# ControlUnit_2.net
KiCad netlist of a schematic drawn in EAGLE
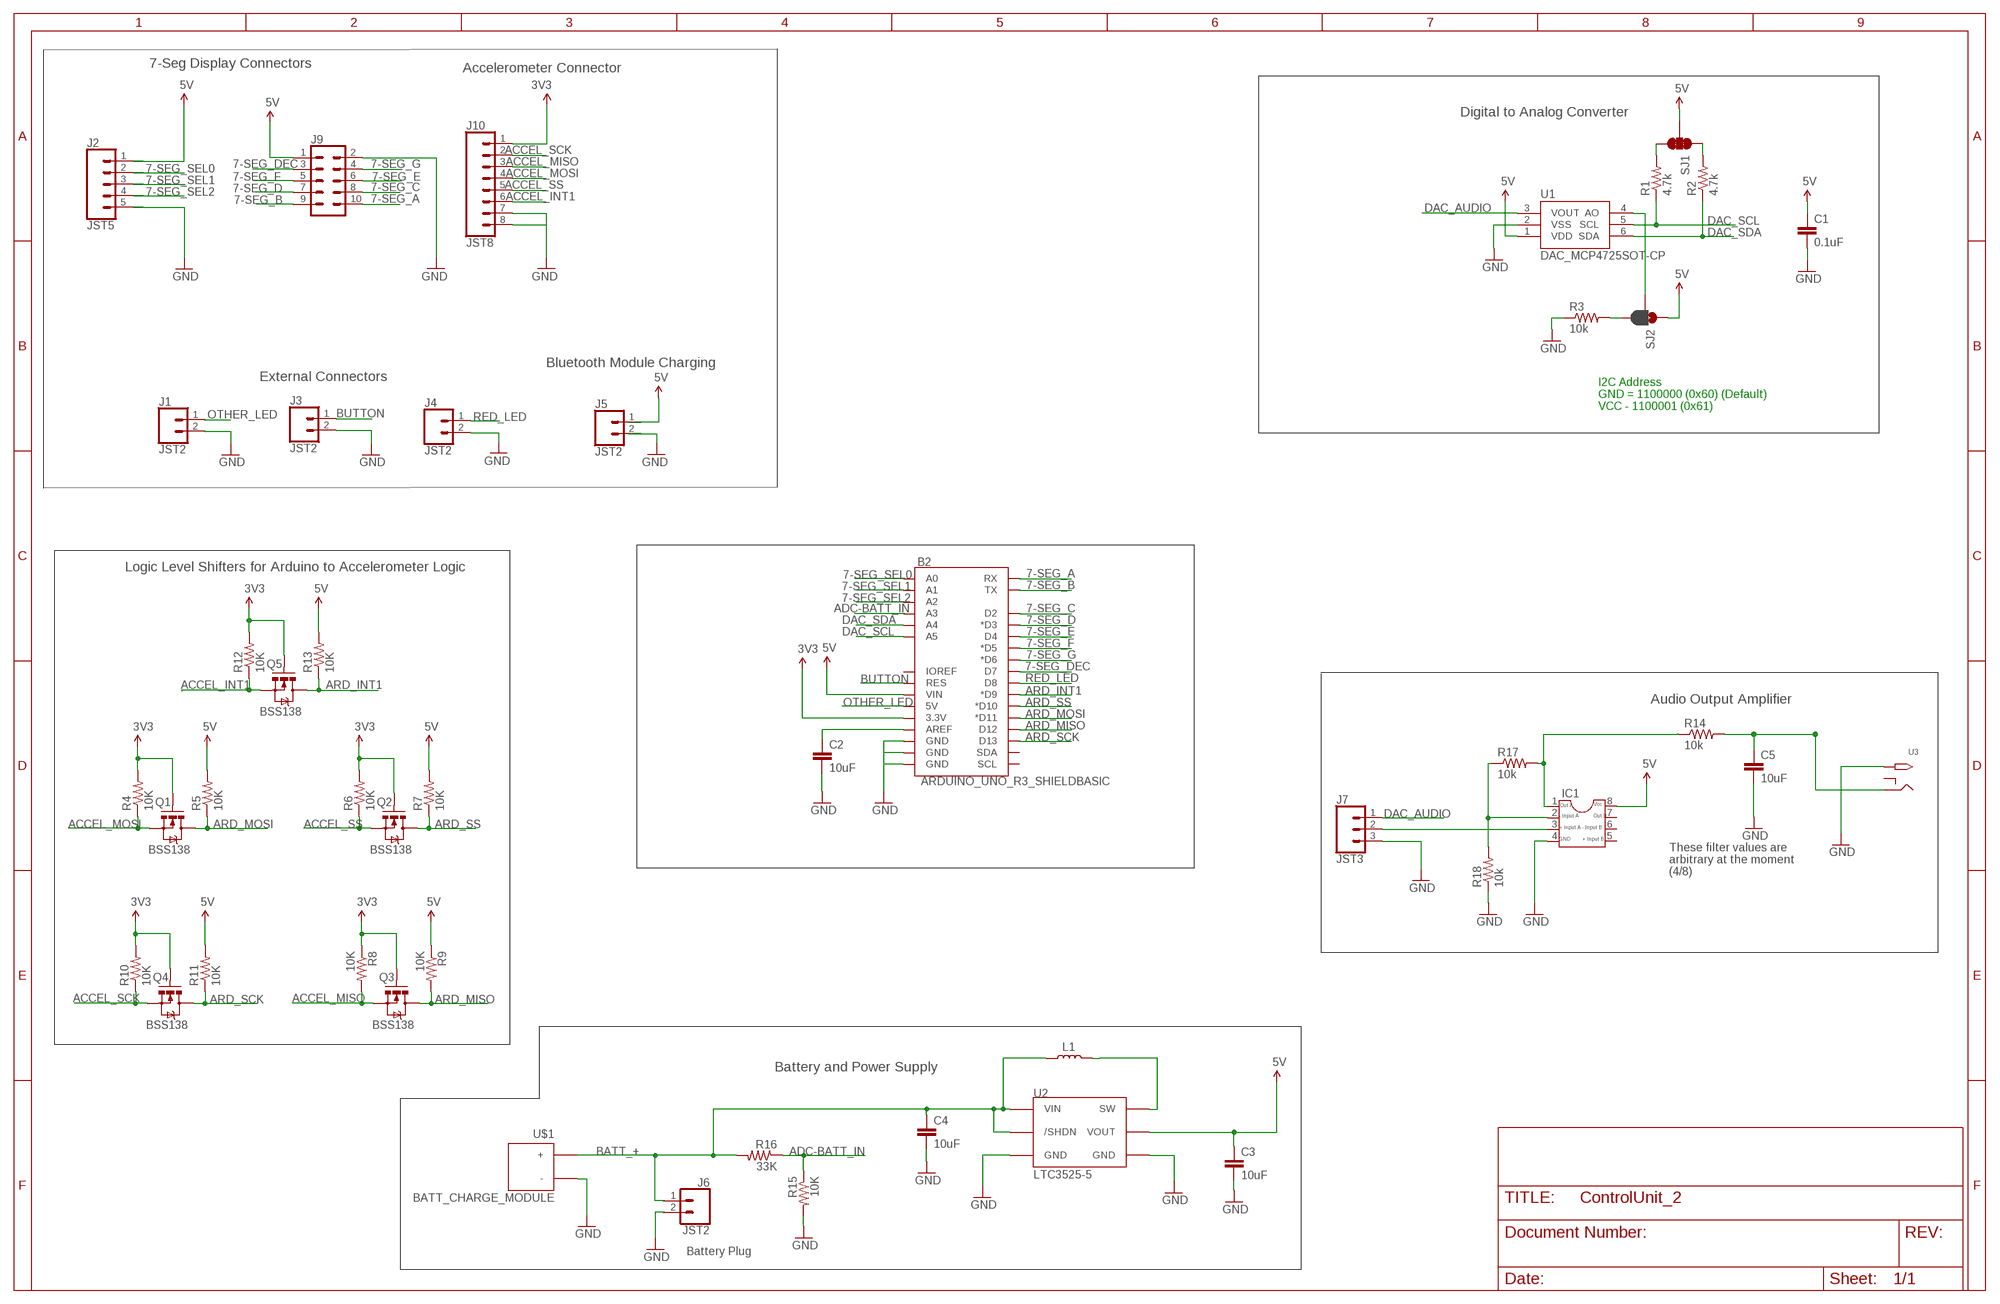
[diagram p0: schematic, sheet 1]

(export (version "E")
  (design (tool "Eeschema 10.0.6"))
  (components
    (comp (ref "B2")
      (value "ARDUINO_UNO_R3_SHIELDBASIC")
      (footprint "eagle-import:UNO_R3_SHIELD")
      (libsource (lib "eagle-import") (part "ARDUINO_UNO_R3_SHIELDBASIC"))
    )
    (comp (ref "C1")
      (value "0.1uF")
      (footprint "eagle-import:0603-CAP")
      (libsource (lib "eagle-import") (part "CAP0603-CAP"))
    )
    (comp (ref "C2")
      (value "10uF")
      (footprint "eagle-import:SPARKFUN_0805")
      (libsource (lib "eagle-import") (part "SPARKFUN_CAP0805"))
    )
    (comp (ref "C3")
      (value "10uF")
      (footprint "eagle-import:0603-CAP")
      (libsource (lib "eagle-import") (part "CAP0603-CAP"))
    )
    (comp (ref "C4")
      (value "10uF")
      (footprint "eagle-import:SPARKFUN_0805")
      (libsource (lib "eagle-import") (part "SPARKFUN_CAP0805"))
    )
    (comp (ref "C5")
      (value "10uF")
      (footprint "eagle-import:0603-CAP")
      (libsource (lib "eagle-import") (part "CAP0603-CAP"))
    )
    (comp (ref "IC1")
      (value "DIL8")
      (footprint "eagle-import:DIL08")
      (libsource (lib "eagle-import") (part "DIL8"))
    )
    (comp (ref "J1")
      (value "JST2")
      (footprint "eagle-import:2JST")
      (libsource (lib "eagle-import") (part "JST2"))
    )
    (comp (ref "J2")
      (value "JST5")
      (footprint "eagle-import:5JST")
      (libsource (lib "eagle-import") (part "JST5"))
    )
    (comp (ref "J3")
      (value "JST2")
      (footprint "eagle-import:2JST")
      (libsource (lib "eagle-import") (part "JST2"))
    )
    (comp (ref "J4")
      (value "JST2")
      (footprint "eagle-import:2JST")
      (libsource (lib "eagle-import") (part "JST2"))
    )
    (comp (ref "J5")
      (value "JST2")
      (footprint "eagle-import:2JST")
      (libsource (lib "eagle-import") (part "JST2"))
    )
    (comp (ref "J6")
      (value "JST2")
      (footprint "eagle-import:2JST")
      (libsource (lib "eagle-import") (part "JST2"))
    )
    (comp (ref "J7")
      (value "JST3")
      (footprint "eagle-import:3JST")
      (libsource (lib "eagle-import") (part "JST3"))
    )
    (comp (ref "J9")
      (value "CONN_05X2SHD_LOCK")
      (footprint "eagle-import:2X5-SHROUDED_LOCK")
      (libsource (lib "eagle-import") (part "CONN_05X2SHD_LOCK"))
    )
    (comp (ref "J10")
      (value "JST8")
      (footprint "eagle-import:8JST")
      (libsource (lib "eagle-import") (part "JST8"))
    )
    (comp (ref "L1")
      (value "10uH")
      (footprint "eagle-import:1210")
      (libsource (lib "eagle-import") (part "INDUCTOR"))
    )
    (comp (ref "Q1")
      (value "BSS138")
      (footprint "eagle-import:SOT23-3")
      (libsource (lib "eagle-import") (part "MOSFET-NCHANNELSMD"))
    )
    (comp (ref "Q2")
      (value "BSS138")
      (footprint "eagle-import:SOT23-3")
      (libsource (lib "eagle-import") (part "MOSFET-NCHANNELSMD"))
    )
    (comp (ref "Q3")
      (value "BSS138")
      (footprint "eagle-import:SOT23-3")
      (libsource (lib "eagle-import") (part "MOSFET-NCHANNELSMD"))
    )
    (comp (ref "Q4")
      (value "BSS138")
      (footprint "eagle-import:SOT23-3")
      (libsource (lib "eagle-import") (part "MOSFET-NCHANNELSMD"))
    )
    (comp (ref "Q5")
      (value "BSS138")
      (footprint "eagle-import:SOT23-3")
      (libsource (lib "eagle-import") (part "MOSFET-NCHANNELSMD"))
    )
    (comp (ref "R1")
      (value "4.7k")
      (footprint "eagle-import:0603-RES")
      (libsource (lib "eagle-import") (part "RESISTOR0603-RES"))
    )
    (comp (ref "R2")
      (value "4.7k")
      (footprint "eagle-import:0603-RES")
      (libsource (lib "eagle-import") (part "RESISTOR0603-RES"))
    )
    (comp (ref "R3")
      (value "10k")
      (footprint "eagle-import:0603-RES")
      (libsource (lib "eagle-import") (part "RESISTOR0603-RES"))
    )
    (comp (ref "R4")
      (value "10K")
      (footprint "eagle-import:SPARKFUN_0603-RES")
      (libsource (lib "eagle-import") (part "SPARKFUN_RESISTOR0603-RES"))
    )
    (comp (ref "R5")
      (value "10K")
      (footprint "eagle-import:SPARKFUN_0603-RES")
      (libsource (lib "eagle-import") (part "SPARKFUN_RESISTOR0603-RES"))
    )
    (comp (ref "R6")
      (value "10K")
      (footprint "eagle-import:SPARKFUN_0603-RES")
      (libsource (lib "eagle-import") (part "SPARKFUN_RESISTOR0603-RES"))
    )
    (comp (ref "R7")
      (value "10K")
      (footprint "eagle-import:SPARKFUN_0603-RES")
      (libsource (lib "eagle-import") (part "SPARKFUN_RESISTOR0603-RES"))
    )
    (comp (ref "R8")
      (value "10K")
      (footprint "eagle-import:0603-RES")
      (libsource (lib "eagle-import") (part "RESISTOR0603-RES"))
    )
    (comp (ref "R9")
      (value "10K")
      (footprint "eagle-import:0603-RES")
      (libsource (lib "eagle-import") (part "RESISTOR0603-RES"))
    )
    (comp (ref "R10")
      (value "10K")
      (footprint "eagle-import:SPARKFUN_0603-RES")
      (libsource (lib "eagle-import") (part "SPARKFUN_RESISTOR0603-RES"))
    )
    (comp (ref "R11")
      (value "10K")
      (footprint "eagle-import:SPARKFUN_0603-RES")
      (libsource (lib "eagle-import") (part "SPARKFUN_RESISTOR0603-RES"))
    )
    (comp (ref "R12")
      (value "10K")
      (footprint "eagle-import:SPARKFUN_0603-RES")
      (libsource (lib "eagle-import") (part "SPARKFUN_RESISTOR0603-RES"))
    )
    (comp (ref "R13")
      (value "10K")
      (footprint "eagle-import:SPARKFUN_0603-RES")
      (libsource (lib "eagle-import") (part "SPARKFUN_RESISTOR0603-RES"))
    )
    (comp (ref "R14")
      (value "10k")
      (footprint "eagle-import:0603-RES")
      (libsource (lib "eagle-import") (part "RESISTOR0603-RES"))
    )
    (comp (ref "R15")
      (value "10K")
      (footprint "eagle-import:0603-RES")
      (libsource (lib "eagle-import") (part "RESISTOR0603-RES"))
    )
    (comp (ref "R16")
      (value "33K")
      (footprint "eagle-import:0603-RES")
      (libsource (lib "eagle-import") (part "RESISTOR0603-RES"))
    )
    (comp (ref "R17")
      (value "10k")
      (footprint "eagle-import:0603-RES")
      (libsource (lib "eagle-import") (part "RESISTOR0603-RES"))
    )
    (comp (ref "R18")
      (value "10k")
      (footprint "eagle-import:0603-RES")
      (libsource (lib "eagle-import") (part "RESISTOR0603-RES"))
    )
    (comp (ref "SJ1")
      (value "JUMPER-PAD-3-NC_BY_TRACE")
      (footprint "eagle-import:PAD-JUMPER-3-3OF3_NC_BY_TRACE_YES_SILK_FULL_BOX")
      (libsource (lib "eagle-import") (part "JUMPER-PAD-3-NC_BY_TRACE"))
    )
    (comp (ref "SJ2")
      (value "JUMPER-PAD-3-2OF3_NC_BY_PASTE")
      (footprint "eagle-import:PAD-JUMPER-3-2OF3_NC_BY_PASTE_YES_SILK_FULL_BOX")
      (libsource (lib "eagle-import") (part "JUMPER-PAD-3-2OF3_NC_BY_PASTE"))
    )
    (comp (ref "U$1")
      (value "BATT_CHARGE_MODULE")
      (footprint "eagle-import:BATT_CHARGE_MODULE")
      (libsource (lib "eagle-import") (part "BATT_CHARGE_MODULE"))
    )
    (comp (ref "U1")
      (value "DAC_MCP4725SOT-CP")
      (footprint "eagle-import:SOT23-6-MCP4725")
      (libsource (lib "eagle-import") (part "DAC_MCP4725SOT-CP"))
    )
    (comp (ref "U2")
      (value "LTC3525-5")
      (footprint "eagle-import:LTC3525-5")
      (libsource (lib "eagle-import") (part "LTC3525-5"))
    )
    (comp (ref "U3")
      (value "MONO_JACK")
      (footprint "eagle-import:MONO_JACK")
      (fields (field (name "MANF") "CUI Inc."))
      (libsource (lib "eagle-import") (part "MONO_JACK"))
    )
  )
  (nets
    (net (code "1") (name "/7-SEG_A") (class "Default")
      (node (ref "B2") (pin "RX") (pinfunction "RX_RX") (pintype "bidirectional"))
      (node (ref "J9") (pin "10") (pinfunction "10_10") (pintype "passive"))
    )
    (net (code "2") (name "/7-SEG_B") (class "Default")
      (node (ref "B2") (pin "TX") (pinfunction "TX_TX") (pintype "bidirectional"))
      (node (ref "J9") (pin "9") (pinfunction "9_9") (pintype "passive"))
    )
    (net (code "3") (name "/7-SEG_C") (class "Default")
      (node (ref "B2") (pin "D2") (pinfunction "D2_D2") (pintype "bidirectional"))
      (node (ref "J9") (pin "8") (pinfunction "8_8") (pintype "passive"))
    )
    (net (code "4") (name "/7-SEG_D") (class "Default")
      (node (ref "B2") (pin "D3") (pinfunction "*D3_D3") (pintype "bidirectional"))
      (node (ref "J9") (pin "7") (pinfunction "7_7") (pintype "passive"))
    )
    (net (code "5") (name "/7-SEG_DEC") (class "Default")
      (node (ref "B2") (pin "D7") (pinfunction "D7_D7") (pintype "bidirectional"))
      (node (ref "J9") (pin "3") (pinfunction "3_3") (pintype "passive"))
    )
    (net (code "6") (name "/7-SEG_E") (class "Default")
      (node (ref "B2") (pin "D4") (pinfunction "D4_D4") (pintype "bidirectional"))
      (node (ref "J9") (pin "6") (pinfunction "6_6") (pintype "passive"))
    )
    (net (code "7") (name "/7-SEG_F") (class "Default")
      (node (ref "B2") (pin "D5") (pinfunction "*D5_D5") (pintype "bidirectional"))
      (node (ref "J9") (pin "5") (pinfunction "5_5") (pintype "passive"))
    )
    (net (code "8") (name "/7-SEG_G") (class "Default")
      (node (ref "B2") (pin "D6") (pinfunction "*D6_D6") (pintype "bidirectional"))
      (node (ref "J9") (pin "4") (pinfunction "4_4") (pintype "passive"))
    )
    (net (code "9") (name "/7-SEG_SEL0") (class "Default")
      (node (ref "B2") (pin "A0") (pinfunction "A0_A0") (pintype "bidirectional"))
      (node (ref "J2") (pin "2") (pinfunction "2_2") (pintype "passive"))
    )
    (net (code "10") (name "/7-SEG_SEL1") (class "Default")
      (node (ref "B2") (pin "A1") (pinfunction "A1_A1") (pintype "bidirectional"))
      (node (ref "J2") (pin "3") (pinfunction "3_3") (pintype "passive"))
    )
    (net (code "11") (name "/7-SEG_SEL2") (class "Default")
      (node (ref "B2") (pin "A2") (pinfunction "A2_A2") (pintype "bidirectional"))
      (node (ref "J2") (pin "4") (pinfunction "4_4") (pintype "passive"))
    )
    (net (code "12") (name "/ACCEL_INT1") (class "Default")
      (node (ref "J10") (pin "6") (pinfunction "6_6") (pintype "passive"))
      (node (ref "Q5") (pin "2") (pinfunction "S_2") (pintype "passive"))
      (node (ref "R12") (pin "1") (pinfunction "1_1") (pintype "passive"))
    )
    (net (code "13") (name "/ACCEL_MISO") (class "Default")
      (node (ref "J10") (pin "3") (pinfunction "3_3") (pintype "passive"))
      (node (ref "Q3") (pin "2") (pinfunction "S_2") (pintype "passive"))
      (node (ref "R8") (pin "2") (pinfunction "2_2") (pintype "passive"))
    )
    (net (code "14") (name "/ACCEL_MOSI") (class "Default")
      (node (ref "J10") (pin "4") (pinfunction "4_4") (pintype "passive"))
      (node (ref "Q1") (pin "2") (pinfunction "S_2") (pintype "passive"))
      (node (ref "R4") (pin "1") (pinfunction "1_1") (pintype "passive"))
    )
    (net (code "15") (name "/ACCEL_SCK") (class "Default")
      (node (ref "J10") (pin "2") (pinfunction "2_2") (pintype "passive"))
      (node (ref "Q4") (pin "2") (pinfunction "S_2") (pintype "passive"))
      (node (ref "R10") (pin "1") (pinfunction "1_1") (pintype "passive"))
    )
    (net (code "16") (name "/ACCEL_SS") (class "Default")
      (node (ref "J10") (pin "5") (pinfunction "5_5") (pintype "passive"))
      (node (ref "Q2") (pin "2") (pinfunction "S_2") (pintype "passive"))
      (node (ref "R6") (pin "1") (pinfunction "1_1") (pintype "passive"))
    )
    (net (code "17") (name "/ADC-BATT_IN") (class "Default")
      (node (ref "B2") (pin "A3") (pinfunction "A3_A3") (pintype "bidirectional"))
      (node (ref "R15") (pin "1") (pinfunction "1_1") (pintype "passive"))
      (node (ref "R16") (pin "1") (pinfunction "1_1") (pintype "passive"))
    )
    (net (code "18") (name "/ARD_INT1") (class "Default")
      (node (ref "B2") (pin "D9") (pinfunction "*D9_D9") (pintype "bidirectional"))
      (node (ref "Q5") (pin "3") (pinfunction "D_3") (pintype "passive"))
      (node (ref "R13") (pin "1") (pinfunction "1_1") (pintype "passive"))
    )
    (net (code "19") (name "/ARD_MISO") (class "Default")
      (node (ref "B2") (pin "D12") (pinfunction "D12_D12") (pintype "bidirectional"))
      (node (ref "Q3") (pin "3") (pinfunction "D_3") (pintype "passive"))
      (node (ref "R9") (pin "2") (pinfunction "2_2") (pintype "passive"))
    )
    (net (code "20") (name "/ARD_MOSI") (class "Default")
      (node (ref "B2") (pin "D11") (pinfunction "*D11_D11") (pintype "bidirectional"))
      (node (ref "Q1") (pin "3") (pinfunction "D_3") (pintype "passive"))
      (node (ref "R5") (pin "1") (pinfunction "1_1") (pintype "passive"))
    )
    (net (code "21") (name "/ARD_SCK") (class "Default")
      (node (ref "B2") (pin "D13") (pinfunction "D13_D13") (pintype "bidirectional"))
      (node (ref "Q4") (pin "3") (pinfunction "D_3") (pintype "passive"))
      (node (ref "R11") (pin "1") (pinfunction "1_1") (pintype "passive"))
    )
    (net (code "22") (name "/ARD_SS") (class "Default")
      (node (ref "B2") (pin "D10") (pinfunction "*D10_D10") (pintype "bidirectional"))
      (node (ref "Q2") (pin "3") (pinfunction "D_3") (pintype "passive"))
      (node (ref "R7") (pin "1") (pinfunction "1_1") (pintype "passive"))
    )
    (net (code "23") (name "/BATT_+") (class "Default")
      (node (ref "C4") (pin "1") (pinfunction "1_1") (pintype "passive"))
      (node (ref "J6") (pin "1") (pinfunction "1_1") (pintype "passive"))
      (node (ref "L1") (pin "1") (pinfunction "1_1") (pintype "passive"))
      (node (ref "R16") (pin "2") (pinfunction "2_2") (pintype "passive"))
      (node (ref "U$1") (pin "P$2") (pinfunction "+_P$2") (pintype "bidirectional"))
      (node (ref "U2") (pin "1") (pinfunction "/SHDN_1") (pintype "bidirectional"))
      (node (ref "U2") (pin "3") (pinfunction "VIN_3") (pintype "bidirectional"))
    )
    (net (code "24") (name "/BUTTON") (class "Default")
      (node (ref "B2") (pin "RES") (pinfunction "RES_RES") (pintype "bidirectional"))
      (node (ref "J3") (pin "1") (pinfunction "1_1") (pintype "passive"))
    )
    (net (code "25") (name "/DAC_AUDIO") (class "Default")
      (node (ref "J7") (pin "1") (pinfunction "1_1") (pintype "passive"))
      (node (ref "U1") (pin "3") (pinfunction "VOUT_3") (pintype "bidirectional"))
    )
    (net (code "26") (name "/DAC_SCL") (class "Default")
      (node (ref "B2") (pin "A5") (pinfunction "A5_A5") (pintype "bidirectional"))
      (node (ref "R1") (pin "1") (pinfunction "1_1") (pintype "passive"))
      (node (ref "U1") (pin "5") (pinfunction "SCL_5") (pintype "bidirectional"))
    )
    (net (code "27") (name "/DAC_SDA") (class "Default")
      (node (ref "B2") (pin "A4") (pinfunction "A4_A4") (pintype "bidirectional"))
      (node (ref "R2") (pin "1") (pinfunction "1_1") (pintype "passive"))
      (node (ref "U1") (pin "6") (pinfunction "SDA_6") (pintype "bidirectional"))
    )
    (net (code "28") (name "/OTHER_LED") (class "Default")
      (node (ref "B2") (pin "5V") (pinfunction "5V_5V") (pintype "bidirectional"))
      (node (ref "J1") (pin "1") (pinfunction "1_1") (pintype "passive"))
    )
    (net (code "29") (name "/RED_LED") (class "Default")
      (node (ref "B2") (pin "D8") (pinfunction "D8_D8") (pintype "bidirectional"))
      (node (ref "J4") (pin "1") (pinfunction "1_1") (pintype "passive"))
    )
    (net (code "30") (name "3V3") (class "Default")
      (node (ref "B2") (pin "3.3V") (pinfunction "3.3V_3.3V") (pintype "bidirectional"))
      (node (ref "J10") (pin "1") (pinfunction "1_1") (pintype "passive"))
      (node (ref "Q1") (pin "1") (pinfunction "G_1") (pintype "passive"))
      (node (ref "Q2") (pin "1") (pinfunction "G_1") (pintype "passive"))
      (node (ref "Q3") (pin "1") (pinfunction "G_1") (pintype "passive"))
      (node (ref "Q4") (pin "1") (pinfunction "G_1") (pintype "passive"))
      (node (ref "Q5") (pin "1") (pinfunction "G_1") (pintype "passive"))
      (node (ref "R10") (pin "2") (pinfunction "2_2") (pintype "passive"))
      (node (ref "R12") (pin "2") (pinfunction "2_2") (pintype "passive"))
      (node (ref "R4") (pin "2") (pinfunction "2_2") (pintype "passive"))
      (node (ref "R6") (pin "2") (pinfunction "2_2") (pintype "passive"))
      (node (ref "R8") (pin "1") (pinfunction "1_1") (pintype "passive"))
    )
    (net (code "31") (name "5V") (class "Default")
      (node (ref "B2") (pin "VIN") (pinfunction "VIN_VIN") (pintype "bidirectional"))
      (node (ref "C1") (pin "1") (pinfunction "1_1") (pintype "passive"))
      (node (ref "C3") (pin "1") (pinfunction "1_1") (pintype "passive"))
      (node (ref "IC1") (pin "8") (pinfunction "8_8") (pintype "passive"))
      (node (ref "J2") (pin "1") (pinfunction "1_1") (pintype "passive"))
      (node (ref "J5") (pin "1") (pinfunction "1_1") (pintype "passive"))
      (node (ref "J9") (pin "1") (pinfunction "1_1") (pintype "passive"))
      (node (ref "R11") (pin "2") (pinfunction "2_2") (pintype "passive"))
      (node (ref "R13") (pin "2") (pinfunction "2_2") (pintype "passive"))
      (node (ref "R5") (pin "2") (pinfunction "2_2") (pintype "passive"))
      (node (ref "R7") (pin "2") (pinfunction "2_2") (pintype "passive"))
      (node (ref "R9") (pin "1") (pinfunction "1_1") (pintype "passive"))
      (node (ref "SJ1") (pin "2") (pinfunction "2_2") (pintype "passive"))
      (node (ref "SJ2") (pin "1") (pinfunction "1_1") (pintype "passive"))
      (node (ref "U1") (pin "1") (pinfunction "VDD_1") (pintype "bidirectional"))
      (node (ref "U2") (pin "4") (pinfunction "VOUT_4") (pintype "bidirectional"))
    )
    (net (code "32") (name "GND") (class "Default")
      (node (ref "B2") (pin "GND@0") (pinfunction "GND_GND@0") (pintype "bidirectional"))
      (node (ref "B2") (pin "GND@1") (pinfunction "GND_GND@1") (pintype "bidirectional"))
      (node (ref "B2") (pin "GND@2") (pinfunction "GND_GND@2") (pintype "bidirectional"))
      (node (ref "C1") (pin "2") (pinfunction "2_2") (pintype "passive"))
      (node (ref "C2") (pin "2") (pinfunction "2_2") (pintype "passive"))
      (node (ref "C3") (pin "2") (pinfunction "2_2") (pintype "passive"))
      (node (ref "C4") (pin "2") (pinfunction "2_2") (pintype "passive"))
      (node (ref "C5") (pin "2") (pinfunction "2_2") (pintype "passive"))
      (node (ref "IC1") (pin "4") (pinfunction "4_4") (pintype "passive"))
      (node (ref "J1") (pin "2") (pinfunction "2_2") (pintype "passive"))
      (node (ref "J10") (pin "7") (pinfunction "7_7") (pintype "passive"))
      (node (ref "J10") (pin "8") (pinfunction "8_8") (pintype "passive"))
      (node (ref "J2") (pin "5") (pinfunction "5_5") (pintype "passive"))
      (node (ref "J3") (pin "2") (pinfunction "2_2") (pintype "passive"))
      (node (ref "J4") (pin "2") (pinfunction "2_2") (pintype "passive"))
      (node (ref "J5") (pin "2") (pinfunction "2_2") (pintype "passive"))
      (node (ref "J6") (pin "2") (pinfunction "2_2") (pintype "passive"))
      (node (ref "J7") (pin "3") (pinfunction "3_3") (pintype "passive"))
      (node (ref "J9") (pin "2") (pinfunction "2_2") (pintype "passive"))
      (node (ref "R15") (pin "2") (pinfunction "2_2") (pintype "passive"))
      (node (ref "R18") (pin "1") (pinfunction "1_1") (pintype "passive"))
      (node (ref "R3") (pin "1") (pinfunction "1_1") (pintype "passive"))
      (node (ref "U$1") (pin "P$1") (pinfunction "-_P$1") (pintype "bidirectional"))
      (node (ref "U1") (pin "2") (pinfunction "VSS_2") (pintype "bidirectional"))
      (node (ref "U2") (pin "2") (pinfunction "GND_2") (pintype "bidirectional"))
      (node (ref "U2") (pin "5") (pinfunction "GND_5") (pintype "bidirectional"))
      (node (ref "U3") (pin "1") (pinfunction "1_1") (pintype "bidirectional"))
    )
    (net (code "33") (name "Net-(B2-PadAREF)") (class "Default")
      (node (ref "B2") (pin "AREF") (pinfunction "AREF_AREF") (pintype "bidirectional"))
      (node (ref "C2") (pin "1") (pinfunction "1_1") (pintype "passive"))
    )
    (net (code "34") (name "Net-(C5-Pad1)") (class "Default")
      (node (ref "C5") (pin "1") (pinfunction "1_1") (pintype "passive"))
      (node (ref "R14") (pin "2") (pinfunction "2_2") (pintype "passive"))
      (node (ref "U3") (pin "2") (pinfunction "2_2") (pintype "bidirectional"))
    )
    (net (code "35") (name "Net-(IC1-Pad1)") (class "Default")
      (node (ref "IC1") (pin "1") (pinfunction "1_1") (pintype "passive"))
      (node (ref "R14") (pin "1") (pinfunction "1_1") (pintype "passive"))
      (node (ref "R17") (pin "2") (pinfunction "2_2") (pintype "passive"))
    )
    (net (code "36") (name "Net-(IC1-Pad2)") (class "Default")
      (node (ref "IC1") (pin "2") (pinfunction "2_2") (pintype "passive"))
      (node (ref "R17") (pin "1") (pinfunction "1_1") (pintype "passive"))
      (node (ref "R18") (pin "2") (pinfunction "2_2") (pintype "passive"))
    )
    (net (code "37") (name "Net-(IC1-Pad3)") (class "Default")
      (node (ref "IC1") (pin "3") (pinfunction "3_3") (pintype "passive"))
      (node (ref "J7") (pin "2") (pinfunction "2_2") (pintype "passive"))
    )
    (net (code "38") (name "Net-(R1-Pad2)") (class "Default")
      (node (ref "R1") (pin "2") (pinfunction "2_2") (pintype "passive"))
      (node (ref "SJ1") (pin "3") (pinfunction "3_3") (pintype "passive"))
    )
    (net (code "39") (name "Net-(R2-Pad2)") (class "Default")
      (node (ref "R2") (pin "2") (pinfunction "2_2") (pintype "passive"))
      (node (ref "SJ1") (pin "1") (pinfunction "1_1") (pintype "passive"))
    )
    (net (code "40") (name "Net-(R3-Pad2)") (class "Default")
      (node (ref "R3") (pin "2") (pinfunction "2_2") (pintype "passive"))
      (node (ref "SJ2") (pin "3") (pinfunction "3_3") (pintype "passive"))
    )
    (net (code "41") (name "Net-(U1-AO)") (class "Default")
      (node (ref "SJ2") (pin "2") (pinfunction "2_2") (pintype "passive"))
      (node (ref "U1") (pin "4") (pinfunction "AO_4") (pintype "bidirectional"))
    )
    (net (code "42") (name "Net-(U2-SW)") (class "Default")
      (node (ref "L1") (pin "2") (pinfunction "2_2") (pintype "passive"))
      (node (ref "U2") (pin "6") (pinfunction "SW_6") (pintype "bidirectional"))
    )
    (net (code "43") (name "unconnected-(B2-PadIOREF)") (class "Default")
      (node (ref "B2") (pin "IOREF") (pinfunction "IOREF_IOREF") (pintype "bidirectional"))
    )
    (net (code "44") (name "unconnected-(B2-PadSCL)") (class "Default")
      (node (ref "B2") (pin "SCL") (pinfunction "SCL_SCL") (pintype "bidirectional"))
    )
    (net (code "45") (name "unconnected-(B2-PadSDA)") (class "Default")
      (node (ref "B2") (pin "SDA") (pinfunction "SDA_SDA") (pintype "bidirectional"))
    )
    (net (code "46") (name "unconnected-(IC1-Pad5)") (class "Default")
      (node (ref "IC1") (pin "5") (pinfunction "5_5") (pintype "passive"))
    )
    (net (code "47") (name "unconnected-(IC1-Pad6)") (class "Default")
      (node (ref "IC1") (pin "6") (pinfunction "6_6") (pintype "passive"))
    )
    (net (code "48") (name "unconnected-(IC1-Pad7)") (class "Default")
      (node (ref "IC1") (pin "7") (pinfunction "7_7") (pintype "passive"))
    )
    (net (code "49") (name "unconnected-(U3-Pad3)") (class "Default")
      (node (ref "U3") (pin "3") (pinfunction "3_3") (pintype "bidirectional"))
    )
  )
)
